# esp32_controller.net
KiCad netlist of a schematic drawn in Altium Designer
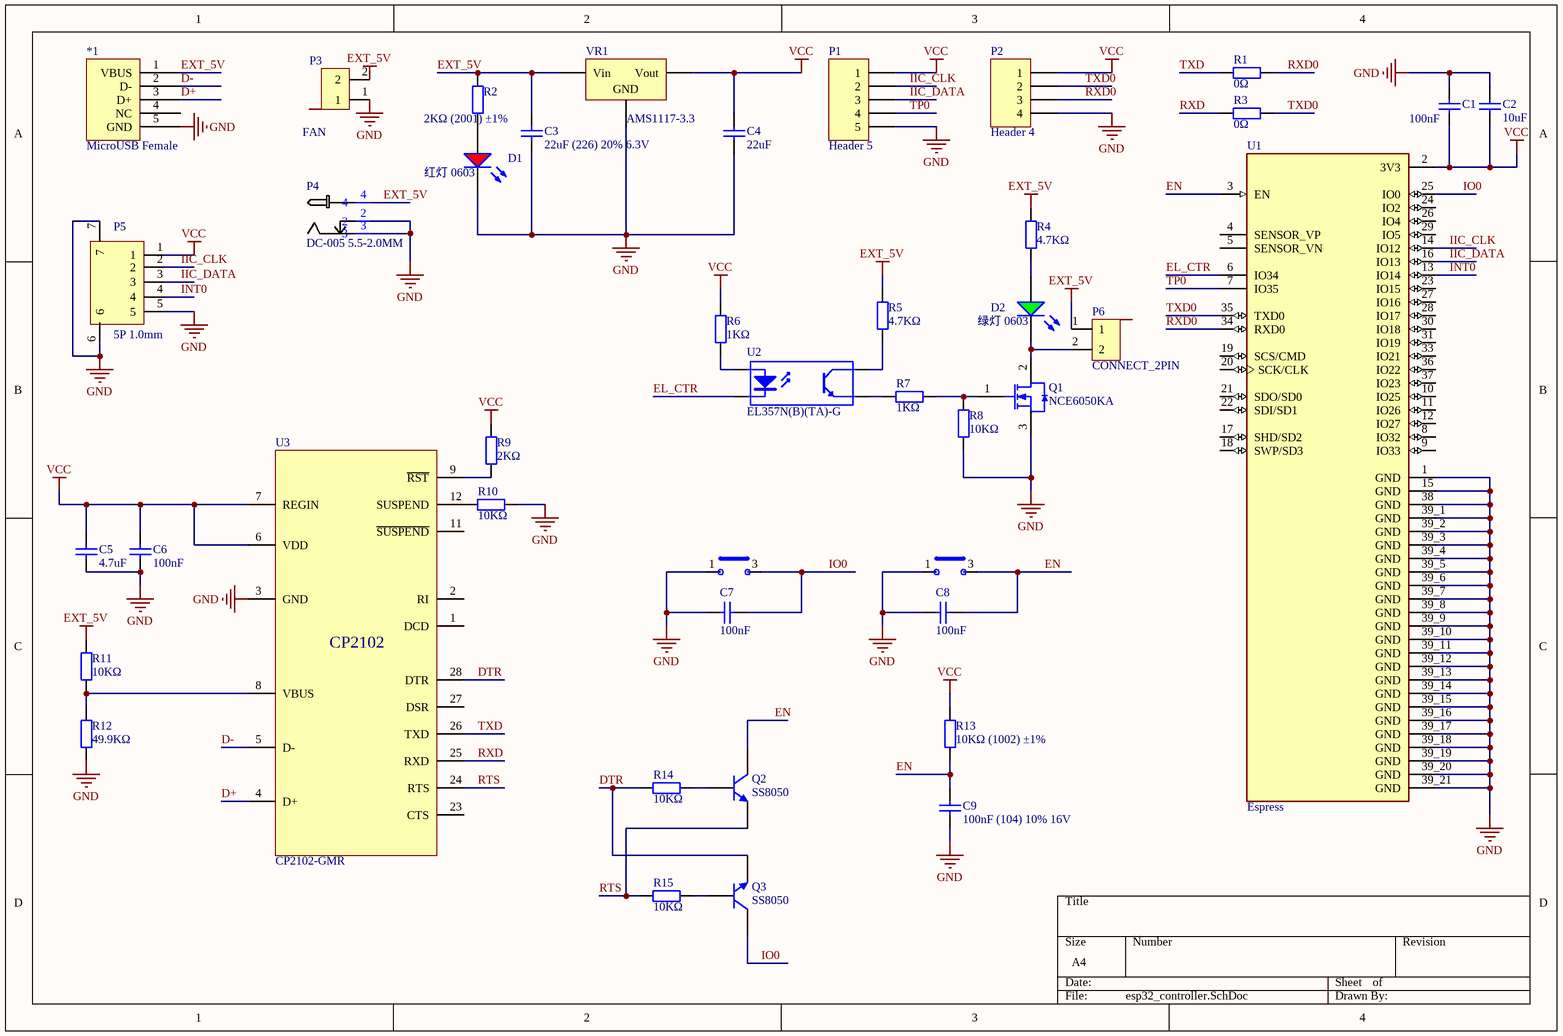
[diagram p0: esp32_controller.SchDoc]

(export (version "E")
  (design (tool "Eeschema 10.0.6"))
  (components
    (comp (ref "*1")
      (value "MicroUSB Female")
      (footprint "MicroUSB Female")
      (libsource (lib "Miscellaneous Devices LC") (part "MicroUSB Female"))
    )
    (comp (ref "C1")
      (value "100nF")
      (footprint "0402_C")
      (description "贴片电容")
      (libsource (lib "Miscellaneous Devices LC") (part "0402 100nF (104) 10% 16V"))
    )
    (comp (ref "C2")
      (value "10uF")
      (footprint "0603_C")
      (description "贴片电容")
      (libsource (lib "Miscellaneous Devices LC") (part "0603 10uF (106) 10% 10V"))
    )
    (comp (ref "C3")
      (value "22uF (226) 20% 6.3V")
      (footprint "0603_C")
      (description "贴片电容")
      (libsource (lib "Miscellaneous Devices LC") (part "0603 22uF (226) 20% 6.3V"))
    )
    (comp (ref "C4")
      (value "22uF")
      (footprint "0603_C")
      (description "贴片电容")
      (libsource (lib "Miscellaneous Devices LC") (part "0603 22uF (226) 20% 6.3V"))
    )
    (comp (ref "C5")
      (value "4.7uF")
      (footprint "0603_C")
      (description "贴片电容")
      (libsource (lib "Miscellaneous Devices LC") (part "0603 4.7uF (475) 10% 16V"))
    )
    (comp (ref "C6")
      (value "100nF")
      (footprint "0603_C")
      (description "贴片电容")
      (libsource (lib "Miscellaneous Devices LC") (part "0603 100nF (104) 10% 50V"))
    )
    (comp (ref "C7")
      (value "100nF")
      (footprint "0402_C")
      (description "贴片电容")
      (libsource (lib "Miscellaneous Devices LC") (part "0402 100nF (104) 10% 16V"))
    )
    (comp (ref "C8")
      (value "100nF")
      (footprint "0402_C")
      (description "贴片电容")
      (libsource (lib "Miscellaneous Devices LC") (part "0402 100nF (104) 10% 16V"))
    )
    (comp (ref "C9")
      (value "100nF (104) 10% 16V")
      (footprint "0402_C")
      (description "贴片电容")
      (libsource (lib "Miscellaneous Devices LC") (part "0402 100nF (104) 10% 16V"))
    )
    (comp (ref "D1")
      (value "红灯 0603")
      (footprint "0603_LED_S1")
      (description "发光二极管")
      (libsource (lib "Miscellaneous Devices LC") (part "0603 红灯"))
    )
    (comp (ref "D2")
      (value "绿灯 0603")
      (footprint "0603_LED_S1")
      (description "发光二极管")
      (libsource (lib "Miscellaneous Devices LC") (part "0603 绿灯"))
    )
    (comp (ref "P1")
      (value "Header 5")
      (footprint "HDR1X5")
      (description "Header, 5-Pin")
      (fields (field (name "PUBLISHER") "Altium Limited"))
      (libsource (lib "Miscellaneous Connectors") (part "Header 5"))
    )
    (comp (ref "P2")
      (value "Header 4")
      (footprint "HDR1X4")
      (description "Header, 4-Pin")
      (fields (field (name "PUBLISHER") "Altium Limited"))
      (libsource (lib "Miscellaneous Connectors") (part "Header 4"))
    )
    (comp (ref "P3")
      (value "FAN")
      (footprint "CONNECT_2PIN")
      (description "欧式接线端子 间距5MM")
      (libsource (lib "Miscellaneous Devices LC") (part "CONNECT_2PIN"))
    )
    (comp (ref "P4")
      (value "DC-005 5.5-2.0MM")
      (footprint "DC-005")
      (description "DC-005 5.5-2.0MM 铁材质")
      (libsource (lib "Miscellaneous Devices LC") (part "DC-005 5.5-2.0MM"))
    )
    (comp (ref "P5")
      (value "5P 1.0mm")
      (footprint "FPC 1.00MM CONNECTOR SMT")
      (description "AFA01-S05FCA-00")
      (libsource (lib "Miscellaneous Devices LC") (part "FPC Connect"))
    )
    (comp (ref "P6")
      (value "CONNECT_2PIN")
      (footprint "CONNECT_2PIN")
      (description "欧式接线端子 间距5MM")
      (libsource (lib "") (part "CONNECT_2PIN_1"))
    )
    (comp (ref "Q1")
      (value "NCE6050KA")
      (footprint "TO-252-2")
      (description "MOS(场效应管) N-Channel")
      (libsource (lib "Miscellaneous Devices LC") (part "NCE6050KA"))
    )
    (comp (ref "Q2")
      (value "SS8050")
      (footprint "SOT-23(SOT-23-3)")
      (description "三极管")
      (libsource (lib "Miscellaneous Devices LC") (part "SOT-23 SS8050 Y1"))
    )
    (comp (ref "Q3")
      (value "SS8050")
      (footprint "SOT-23(SOT-23-3)")
      (description "三极管")
      (libsource (lib "Miscellaneous Devices LC") (part "SOT-23 SS8050 Y1"))
    )
    (comp (ref "R1")
      (value "0Ω")
      (footprint "0402_R")
      (description "贴片电阻")
      (libsource (lib "Miscellaneous Devices LC") (part "0402 0Ω (0R0) 1%"))
    )
    (comp (ref "R2")
      (value "2KΩ (2001) ±1%")
      (footprint "0402_R")
      (description "贴片电阻")
      (libsource (lib "Miscellaneous Devices LC") (part "0402 2KΩ (2001) 1%"))
    )
    (comp (ref "R3")
      (value "0Ω")
      (footprint "0402_R")
      (description "贴片电阻")
      (libsource (lib "Miscellaneous Devices LC") (part "0402 0Ω (0R0) 1%"))
    )
    (comp (ref "R4")
      (value "4.7KΩ")
      (footprint "0805_R")
      (description "贴片电阻")
      (libsource (lib "Miscellaneous Devices LC") (part "0805 4.7KΩ (4701) 1%"))
    )
    (comp (ref "R5")
      (value "4.7KΩ")
      (footprint "0805_R")
      (description "贴片电阻")
      (libsource (lib "Miscellaneous Devices LC") (part "0805 4.7KΩ (4701) 1%"))
    )
    (comp (ref "R6")
      (value "1KΩ")
      (footprint "0402_R")
      (description "贴片电阻")
      (libsource (lib "Miscellaneous Devices LC") (part "0402 1KΩ (1001) 1%"))
    )
    (comp (ref "R7")
      (value "1KΩ")
      (footprint "0805_R")
      (description "贴片电阻")
      (libsource (lib "Miscellaneous Devices LC") (part "0805 1KΩ (1001) 1%"))
    )
    (comp (ref "R8")
      (value "10KΩ")
      (footprint "0805_R")
      (description "贴片电阻")
      (libsource (lib "Miscellaneous Devices LC") (part "0805 10KΩ (1002) 1%"))
    )
    (comp (ref "R9")
      (value "2KΩ")
      (footprint "0402_R")
      (description "贴片电阻")
      (libsource (lib "Miscellaneous Devices LC") (part "0402 2KΩ (2001) 1%"))
    )
    (comp (ref "R10")
      (value "10KΩ")
      (footprint "0402_R")
      (description "贴片电阻")
      (libsource (lib "") (part "0402 10KΩ (1002) 1%_1"))
    )
    (comp (ref "R11")
      (value "10KΩ")
      (footprint "0402_R")
      (description "贴片电阻")
      (libsource (lib "Miscellaneous Devices LC") (part "0402 10KΩ (1002) 1%"))
    )
    (comp (ref "R12")
      (value "49.9KΩ")
      (footprint "0402_R")
      (description "贴片电阻")
      (libsource (lib "Miscellaneous Devices LC") (part "0402 49.9KΩ (4992) 1%"))
    )
    (comp (ref "R13")
      (value "10KΩ (1002) ±1%")
      (footprint "0402_R")
      (description "贴片电阻")
      (libsource (lib "Miscellaneous Devices LC") (part "0402 10KΩ (1002) 1%"))
    )
    (comp (ref "R14")
      (value "10KΩ")
      (footprint "0402_R")
      (description "贴片电阻")
      (libsource (lib "") (part "0402 10KΩ (1002) 1%_1"))
    )
    (comp (ref "R15")
      (value "10KΩ")
      (footprint "0402_R")
      (description "贴片电阻")
      (libsource (lib "") (part "0402 10KΩ (1002) 1%_1"))
    )
    (comp (ref "S1")
      (value "Tactile Switch 轻触开关")
      (footprint "button")
      (libsource (lib "Miscellaneous Devices LC") (part "Button"))
    )
    (comp (ref "S2")
      (value "Tactile Switch 轻触开关")
      (footprint "button")
      (libsource (lib "Miscellaneous Devices LC") (part "Button"))
    )
    (comp (ref "U1")
      (value "Espress")
      (footprint "MODULE_ESP32-WROOM-32D")
      (libsource (lib "Miscellaneous Devices LC") (part "ESP32-WROOM-32D"))
    )
    (comp (ref "U2")
      (value "EL357N(B)(TA)-G")
      (footprint "SOP-4_P2.54")
      (description "贴片光耦")
      (libsource (lib "Miscellaneous Devices LC") (part "EL357N(B)(TA)-G_[C6649]"))
    )
    (comp (ref "U3")
      (value "CP2102-GMR")
      (footprint "QFN-28_5x5x05P")
      (description "USB")
      (libsource (lib "Miscellaneous Devices LC") (part "CP2102-GMR_[C6568]"))
    )
    (comp (ref "VR1")
      (value "AMS1117-3.3")
      (footprint "SOT-223")
      (description "低压差线性稳压(LDO)")
      (libsource (lib "Miscellaneous Devices LC") (part "SOT-223 AMS1117-3.3"))
    )
  )
  (nets
    (net (code "1") (name "/D+") (class "Default")
      (node (ref "*1") (pin "3") (pinfunction "D+_3") (pintype "passive"))
      (node (ref "U3") (pin "4") (pinfunction "D+_4") (pintype "passive"))
    )
    (net (code "2") (name "/D-") (class "Default")
      (node (ref "*1") (pin "2") (pinfunction "D-_2") (pintype "passive"))
      (node (ref "U3") (pin "5") (pinfunction "D-_5") (pintype "passive"))
    )
    (net (code "3") (name "/DTR") (class "Default")
      (node (ref "Q3") (pin "2") (pinfunction "E_2") (pintype "passive"))
      (node (ref "R14") (pin "1") (pinfunction "1_1") (pintype "passive"))
      (node (ref "U3") (pin "28") (pinfunction "DTR_28") (pintype "passive"))
    )
    (net (code "4") (name "/EL_CTR") (class "Default")
      (node (ref "U1") (pin "6") (pinfunction "IO34_6") (pintype "passive"))
      (node (ref "U2") (pin "2") (pinfunction "K_2") (pintype "passive"))
    )
    (net (code "5") (name "/EN") (class "Default")
      (node (ref "C8") (pin "2") (pinfunction "2_2") (pintype "passive"))
      (node (ref "C9") (pin "2") (pinfunction "2_2") (pintype "passive"))
      (node (ref "Q2") (pin "3") (pinfunction "C_3") (pintype "passive"))
      (node (ref "R13") (pin "1") (pinfunction "1_1") (pintype "passive"))
      (node (ref "S2") (pin "3") (pinfunction "3_3") (pintype "passive"))
      (node (ref "U1") (pin "3") (pinfunction "EN_3") (pintype "input"))
    )
    (net (code "6") (name "/IIC_CLK") (class "Default")
      (node (ref "P1") (pin "2") (pinfunction "2_2") (pintype "passive"))
      (node (ref "P5") (pin "2") (pinfunction "2_2") (pintype "passive"))
      (node (ref "U1") (pin "14") (pinfunction "IO12_14") (pintype "bidirectional"))
    )
    (net (code "7") (name "/IIC_DATA") (class "Default")
      (node (ref "P1") (pin "3") (pinfunction "3_3") (pintype "passive"))
      (node (ref "P5") (pin "3") (pinfunction "3_3") (pintype "passive"))
      (node (ref "U1") (pin "16") (pinfunction "IO13_16") (pintype "bidirectional"))
    )
    (net (code "8") (name "/INT0") (class "Default")
      (node (ref "P5") (pin "4") (pinfunction "4_4") (pintype "passive"))
      (node (ref "U1") (pin "13") (pinfunction "IO14_13") (pintype "bidirectional"))
    )
    (net (code "9") (name "/IO0") (class "Default")
      (node (ref "C7") (pin "2") (pinfunction "2_2") (pintype "passive"))
      (node (ref "Q3") (pin "3") (pinfunction "C_3") (pintype "passive"))
      (node (ref "S1") (pin "3") (pinfunction "3_3") (pintype "passive"))
      (node (ref "U1") (pin "25") (pinfunction "IO0_25") (pintype "bidirectional"))
    )
    (net (code "10") (name "/RTS") (class "Default")
      (node (ref "Q2") (pin "2") (pinfunction "E_2") (pintype "passive"))
      (node (ref "R15") (pin "1") (pinfunction "1_1") (pintype "passive"))
      (node (ref "U3") (pin "24") (pinfunction "RTS_24") (pintype "passive"))
    )
    (net (code "11") (name "/RXD") (class "Default")
      (node (ref "R3") (pin "1") (pinfunction "1_1") (pintype "passive"))
      (node (ref "U3") (pin "25") (pinfunction "RXD_25") (pintype "passive"))
    )
    (net (code "12") (name "/RXD0") (class "Default")
      (node (ref "P2") (pin "3") (pinfunction "3_3") (pintype "passive"))
      (node (ref "R1") (pin "2") (pinfunction "2_2") (pintype "passive"))
      (node (ref "U1") (pin "34") (pinfunction "RXD0_34") (pintype "bidirectional"))
    )
    (net (code "13") (name "/TP0") (class "Default")
      (node (ref "P1") (pin "4") (pinfunction "4_4") (pintype "passive"))
      (node (ref "U1") (pin "7") (pinfunction "IO35_7") (pintype "passive"))
    )
    (net (code "14") (name "/TXD") (class "Default")
      (node (ref "R1") (pin "1") (pinfunction "1_1") (pintype "passive"))
      (node (ref "U3") (pin "26") (pinfunction "TXD_26") (pintype "passive"))
    )
    (net (code "15") (name "/TXD0") (class "Default")
      (node (ref "P2") (pin "2") (pinfunction "2_2") (pintype "passive"))
      (node (ref "R3") (pin "2") (pinfunction "2_2") (pintype "passive"))
      (node (ref "U1") (pin "35") (pinfunction "TXD0_35") (pintype "bidirectional"))
    )
    (net (code "16") (name "EXT_5V") (class "Default")
      (node (ref "*1") (pin "1") (pinfunction "VBUS_1") (pintype "passive"))
      (node (ref "C3") (pin "2") (pinfunction "2_2") (pintype "passive"))
      (node (ref "P3") (pin "2") (pinfunction "2_2") (pintype "passive"))
      (node (ref "P4") (pin "4") (pinfunction "4_4") (pintype "passive"))
      (node (ref "P6") (pin "1") (pinfunction "1_1") (pintype "passive"))
      (node (ref "R11") (pin "2") (pinfunction "2_2") (pintype "passive"))
      (node (ref "R2") (pin "2") (pinfunction "2_2") (pintype "passive"))
      (node (ref "R4") (pin "2") (pinfunction "2_2") (pintype "passive"))
      (node (ref "R5") (pin "2") (pinfunction "2_2") (pintype "passive"))
      (node (ref "VR1") (pin "3") (pinfunction "Vin_3") (pintype "passive"))
    )
    (net (code "17") (name "GND") (class "Default")
      (node (ref "*1") (pin "5") (pinfunction "GND_5") (pintype "passive"))
      (node (ref "C1") (pin "2") (pinfunction "2_2") (pintype "passive"))
      (node (ref "C2") (pin "2") (pinfunction "2_2") (pintype "passive"))
      (node (ref "C3") (pin "1") (pinfunction "1_1") (pintype "passive"))
      (node (ref "C4") (pin "1") (pinfunction "1_1") (pintype "passive"))
      (node (ref "C5") (pin "1") (pinfunction "1_1") (pintype "passive"))
      (node (ref "C6") (pin "1") (pinfunction "1_1") (pintype "passive"))
      (node (ref "C7") (pin "1") (pinfunction "1_1") (pintype "passive"))
      (node (ref "C8") (pin "1") (pinfunction "1_1") (pintype "passive"))
      (node (ref "C9") (pin "1") (pinfunction "1_1") (pintype "passive"))
      (node (ref "D1") (pin "K") (pinfunction "K_K") (pintype "passive"))
      (node (ref "P1") (pin "5") (pinfunction "5_5") (pintype "passive"))
      (node (ref "P2") (pin "4") (pinfunction "4_4") (pintype "passive"))
      (node (ref "P3") (pin "1") (pinfunction "1_1") (pintype "passive"))
      (node (ref "P4") (pin "2") (pinfunction "2_2") (pintype "passive"))
      (node (ref "P4") (pin "3") (pinfunction "3_3") (pintype "passive"))
      (node (ref "P5") (pin "5") (pinfunction "5_5") (pintype "passive"))
      (node (ref "P5") (pin "6") (pinfunction "6_6") (pintype "passive"))
      (node (ref "P5") (pin "7") (pinfunction "7_7") (pintype "passive"))
      (node (ref "Q1") (pin "3") (pinfunction "S_3") (pintype "passive"))
      (node (ref "R10") (pin "2") (pinfunction "2_2") (pintype "passive"))
      (node (ref "R12") (pin "1") (pinfunction "1_1") (pintype "passive"))
      (node (ref "R8") (pin "1") (pinfunction "1_1") (pintype "passive"))
      (node (ref "S1") (pin "1") (pinfunction "1_1") (pintype "passive"))
      (node (ref "S2") (pin "1") (pinfunction "1_1") (pintype "passive"))
      (node (ref "U1") (pin "1") (pinfunction "GND_1") (pintype "power_in"))
      (node (ref "U1") (pin "15") (pinfunction "GND_15") (pintype "power_in"))
      (node (ref "U1") (pin "38") (pinfunction "GND_38") (pintype "power_in"))
      (node (ref "U1") (pin "39_1") (pinfunction "GND_39_1") (pintype "power_in"))
      (node (ref "U1") (pin "39_10") (pinfunction "GND_39_10") (pintype "power_in"))
      (node (ref "U1") (pin "39_11") (pinfunction "GND_39_11") (pintype "power_in"))
      (node (ref "U1") (pin "39_12") (pinfunction "GND_39_12") (pintype "power_in"))
      (node (ref "U1") (pin "39_13") (pinfunction "GND_39_13") (pintype "power_in"))
      (node (ref "U1") (pin "39_14") (pinfunction "GND_39_14") (pintype "power_in"))
      (node (ref "U1") (pin "39_15") (pinfunction "GND_39_15") (pintype "power_in"))
      (node (ref "U1") (pin "39_16") (pinfunction "GND_39_16") (pintype "power_in"))
      (node (ref "U1") (pin "39_17") (pinfunction "GND_39_17") (pintype "power_in"))
      (node (ref "U1") (pin "39_18") (pinfunction "GND_39_18") (pintype "power_in"))
      (node (ref "U1") (pin "39_19") (pinfunction "GND_39_19") (pintype "power_in"))
      (node (ref "U1") (pin "39_2") (pinfunction "GND_39_2") (pintype "power_in"))
      (node (ref "U1") (pin "39_20") (pinfunction "GND_39_20") (pintype "power_in"))
      (node (ref "U1") (pin "39_21") (pinfunction "GND_39_21") (pintype "power_in"))
      (node (ref "U1") (pin "39_3") (pinfunction "GND_39_3") (pintype "power_in"))
      (node (ref "U1") (pin "39_4") (pinfunction "GND_39_4") (pintype "power_in"))
      (node (ref "U1") (pin "39_5") (pinfunction "GND_39_5") (pintype "power_in"))
      (node (ref "U1") (pin "39_6") (pinfunction "GND_39_6") (pintype "power_in"))
      (node (ref "U1") (pin "39_7") (pinfunction "GND_39_7") (pintype "power_in"))
      (node (ref "U1") (pin "39_8") (pinfunction "GND_39_8") (pintype "power_in"))
      (node (ref "U1") (pin "39_9") (pinfunction "GND_39_9") (pintype "power_in"))
      (node (ref "U3") (pin "3") (pinfunction "GND_3") (pintype "passive"))
      (node (ref "VR1") (pin "1") (pinfunction "GND_1") (pintype "passive"))
    )
    (net (code "18") (name "Net-(D1-PadA)") (class "Default")
      (node (ref "D1") (pin "A") (pinfunction "A_A") (pintype "passive"))
      (node (ref "R2") (pin "1") (pinfunction "1_1") (pintype "passive"))
    )
    (net (code "19") (name "Net-(D2-PadA)") (class "Default")
      (node (ref "D2") (pin "A") (pinfunction "A_A") (pintype "passive"))
      (node (ref "R4") (pin "1") (pinfunction "1_1") (pintype "passive"))
    )
    (net (code "20") (name "Net-(Q1-D)") (class "Default")
      (node (ref "D2") (pin "K") (pinfunction "K_K") (pintype "passive"))
      (node (ref "P6") (pin "2") (pinfunction "2_2") (pintype "passive"))
      (node (ref "Q1") (pin "2") (pinfunction "D_2") (pintype "passive"))
    )
    (net (code "21") (name "Net-(Q1-G)") (class "Default")
      (node (ref "Q1") (pin "1") (pinfunction "G_1") (pintype "passive"))
      (node (ref "R7") (pin "2") (pinfunction "2_2") (pintype "passive"))
      (node (ref "R8") (pin "2") (pinfunction "2_2") (pintype "passive"))
    )
    (net (code "22") (name "Net-(Q2-B)") (class "Default")
      (node (ref "Q2") (pin "1") (pinfunction "B_1") (pintype "passive"))
      (node (ref "R14") (pin "2") (pinfunction "2_2") (pintype "passive"))
    )
    (net (code "23") (name "Net-(Q3-B)") (class "Default")
      (node (ref "Q3") (pin "1") (pinfunction "B_1") (pintype "passive"))
      (node (ref "R15") (pin "2") (pinfunction "2_2") (pintype "passive"))
    )
    (net (code "24") (name "Net-(U2-A)") (class "Default")
      (node (ref "R6") (pin "1") (pinfunction "1_1") (pintype "passive"))
      (node (ref "U2") (pin "1") (pinfunction "A_1") (pintype "passive"))
    )
    (net (code "25") (name "Net-(U2-C)") (class "Default")
      (node (ref "R5") (pin "1") (pinfunction "1_1") (pintype "passive"))
      (node (ref "U2") (pin "4") (pinfunction "C_4") (pintype "passive"))
    )
    (net (code "26") (name "Net-(U2-E)") (class "Default")
      (node (ref "R7") (pin "1") (pinfunction "1_1") (pintype "passive"))
      (node (ref "U2") (pin "3") (pinfunction "E_3") (pintype "passive"))
    )
    (net (code "27") (name "Net-(U3-SUSPEND)") (class "Default")
      (node (ref "R10") (pin "1") (pinfunction "1_1") (pintype "passive"))
      (node (ref "U3") (pin "12") (pinfunction "SUSPEND_12") (pintype "passive"))
    )
    (net (code "28") (name "Net-(U3-VBUS)") (class "Default")
      (node (ref "R11") (pin "1") (pinfunction "1_1") (pintype "passive"))
      (node (ref "R12") (pin "2") (pinfunction "2_2") (pintype "passive"))
      (node (ref "U3") (pin "8") (pinfunction "VBUS_8") (pintype "passive"))
    )
    (net (code "29") (name "Net-(U3-~{RST})") (class "Default")
      (node (ref "R9") (pin "1") (pinfunction "1_1") (pintype "passive"))
      (node (ref "U3") (pin "9") (pinfunction "~{RST}_9") (pintype "passive"))
    )
    (net (code "30") (name "VCC") (class "Default")
      (node (ref "C1") (pin "1") (pinfunction "1_1") (pintype "passive"))
      (node (ref "C2") (pin "1") (pinfunction "1_1") (pintype "passive"))
      (node (ref "C4") (pin "2") (pinfunction "2_2") (pintype "passive"))
      (node (ref "C5") (pin "2") (pinfunction "2_2") (pintype "passive"))
      (node (ref "C6") (pin "2") (pinfunction "2_2") (pintype "passive"))
      (node (ref "P1") (pin "1") (pinfunction "1_1") (pintype "passive"))
      (node (ref "P2") (pin "1") (pinfunction "1_1") (pintype "passive"))
      (node (ref "P5") (pin "1") (pinfunction "1_1") (pintype "passive"))
      (node (ref "R13") (pin "2") (pinfunction "2_2") (pintype "passive"))
      (node (ref "R6") (pin "2") (pinfunction "2_2") (pintype "passive"))
      (node (ref "R9") (pin "2") (pinfunction "2_2") (pintype "passive"))
      (node (ref "U1") (pin "2") (pinfunction "3V3_2") (pintype "power_in"))
      (node (ref "U3") (pin "6") (pinfunction "VDD_6") (pintype "passive"))
      (node (ref "U3") (pin "7") (pinfunction "REGIN_7") (pintype "passive"))
      (node (ref "VR1") (pin "2") (pinfunction "Vout_2") (pintype "passive"))
    )
    (net (code "31") (name "unconnected-(*1-NC-Pad4)") (class "Default")
      (node (ref "*1") (pin "4") (pinfunction "NC_4") (pintype "passive"))
    )
    (net (code "32") (name "unconnected-(U1-IO2-Pad24)") (class "Default")
      (node (ref "U1") (pin "24") (pinfunction "IO2_24") (pintype "bidirectional"))
    )
    (net (code "33") (name "unconnected-(U1-IO4-Pad26)") (class "Default")
      (node (ref "U1") (pin "26") (pinfunction "IO4_26") (pintype "bidirectional"))
    )
    (net (code "34") (name "unconnected-(U1-IO5-Pad29)") (class "Default")
      (node (ref "U1") (pin "29") (pinfunction "IO5_29") (pintype "bidirectional"))
    )
    (net (code "35") (name "unconnected-(U1-IO15-Pad23)") (class "Default")
      (node (ref "U1") (pin "23") (pinfunction "IO15_23") (pintype "bidirectional"))
    )
    (net (code "36") (name "unconnected-(U1-IO16-Pad27)") (class "Default")
      (node (ref "U1") (pin "27") (pinfunction "IO16_27") (pintype "bidirectional"))
    )
    (net (code "37") (name "unconnected-(U1-IO17-Pad28)") (class "Default")
      (node (ref "U1") (pin "28") (pinfunction "IO17_28") (pintype "bidirectional"))
    )
    (net (code "38") (name "unconnected-(U1-IO18-Pad30)") (class "Default")
      (node (ref "U1") (pin "30") (pinfunction "IO18_30") (pintype "bidirectional"))
    )
    (net (code "39") (name "unconnected-(U1-IO19-Pad31)") (class "Default")
      (node (ref "U1") (pin "31") (pinfunction "IO19_31") (pintype "bidirectional"))
    )
    (net (code "40") (name "unconnected-(U1-IO21-Pad33)") (class "Default")
      (node (ref "U1") (pin "33") (pinfunction "IO21_33") (pintype "bidirectional"))
    )
    (net (code "41") (name "unconnected-(U1-IO22-Pad36)") (class "Default")
      (node (ref "U1") (pin "36") (pinfunction "IO22_36") (pintype "bidirectional"))
    )
    (net (code "42") (name "unconnected-(U1-IO23-Pad37)") (class "Default")
      (node (ref "U1") (pin "37") (pinfunction "IO23_37") (pintype "bidirectional"))
    )
    (net (code "43") (name "unconnected-(U1-IO25-Pad10)") (class "Default")
      (node (ref "U1") (pin "10") (pinfunction "IO25_10") (pintype "bidirectional"))
    )
    (net (code "44") (name "unconnected-(U1-IO26-Pad11)") (class "Default")
      (node (ref "U1") (pin "11") (pinfunction "IO26_11") (pintype "bidirectional"))
    )
    (net (code "45") (name "unconnected-(U1-IO27-Pad12)") (class "Default")
      (node (ref "U1") (pin "12") (pinfunction "IO27_12") (pintype "bidirectional"))
    )
    (net (code "46") (name "unconnected-(U1-IO32-Pad8)") (class "Default")
      (node (ref "U1") (pin "8") (pinfunction "IO32_8") (pintype "bidirectional"))
    )
    (net (code "47") (name "unconnected-(U1-IO33-Pad9)") (class "Default")
      (node (ref "U1") (pin "9") (pinfunction "IO33_9") (pintype "bidirectional"))
    )
    (net (code "48") (name "unconnected-(U1-SCK{slash}CLK-Pad20)") (class "Default")
      (node (ref "U1") (pin "20") (pinfunction "SCK/CLK_20") (pintype "bidirectional"))
    )
    (net (code "49") (name "unconnected-(U1-SCS{slash}CMD-Pad19)") (class "Default")
      (node (ref "U1") (pin "19") (pinfunction "SCS/CMD_19") (pintype "bidirectional"))
    )
    (net (code "50") (name "unconnected-(U1-SDI{slash}SD1-Pad22)") (class "Default")
      (node (ref "U1") (pin "22") (pinfunction "SDI/SD1_22") (pintype "bidirectional"))
    )
    (net (code "51") (name "unconnected-(U1-SDO{slash}SD0-Pad21)") (class "Default")
      (node (ref "U1") (pin "21") (pinfunction "SDO/SD0_21") (pintype "bidirectional"))
    )
    (net (code "52") (name "unconnected-(U1-SENSOR_VN-Pad5)") (class "Default")
      (node (ref "U1") (pin "5") (pinfunction "SENSOR_VN_5") (pintype "passive"))
    )
    (net (code "53") (name "unconnected-(U1-SENSOR_VP-Pad4)") (class "Default")
      (node (ref "U1") (pin "4") (pinfunction "SENSOR_VP_4") (pintype "passive"))
    )
    (net (code "54") (name "unconnected-(U1-SHD{slash}SD2-Pad17)") (class "Default")
      (node (ref "U1") (pin "17") (pinfunction "SHD/SD2_17") (pintype "bidirectional"))
    )
    (net (code "55") (name "unconnected-(U1-SWP{slash}SD3-Pad18)") (class "Default")
      (node (ref "U1") (pin "18") (pinfunction "SWP/SD3_18") (pintype "bidirectional"))
    )
    (net (code "56") (name "unconnected-(U3-CTS-Pad23)") (class "Default")
      (node (ref "U3") (pin "23") (pinfunction "CTS_23") (pintype "passive"))
    )
    (net (code "57") (name "unconnected-(U3-DCD-Pad1)") (class "Default")
      (node (ref "U3") (pin "1") (pinfunction "DCD_1") (pintype "passive"))
    )
    (net (code "58") (name "unconnected-(U3-DSR-Pad27)") (class "Default")
      (node (ref "U3") (pin "27") (pinfunction "DSR_27") (pintype "passive"))
    )
    (net (code "59") (name "unconnected-(U3-RI-Pad2)") (class "Default")
      (node (ref "U3") (pin "2") (pinfunction "RI_2") (pintype "passive"))
    )
    (net (code "60") (name "unconnected-(U3-~{SUSPEND}-Pad11)") (class "Default")
      (node (ref "U3") (pin "11") (pinfunction "~{SUSPEND}_11") (pintype "passive"))
    )
  )
)
